# BSPD_v7b.net
KiCad netlist of a schematic drawn in EAGLE
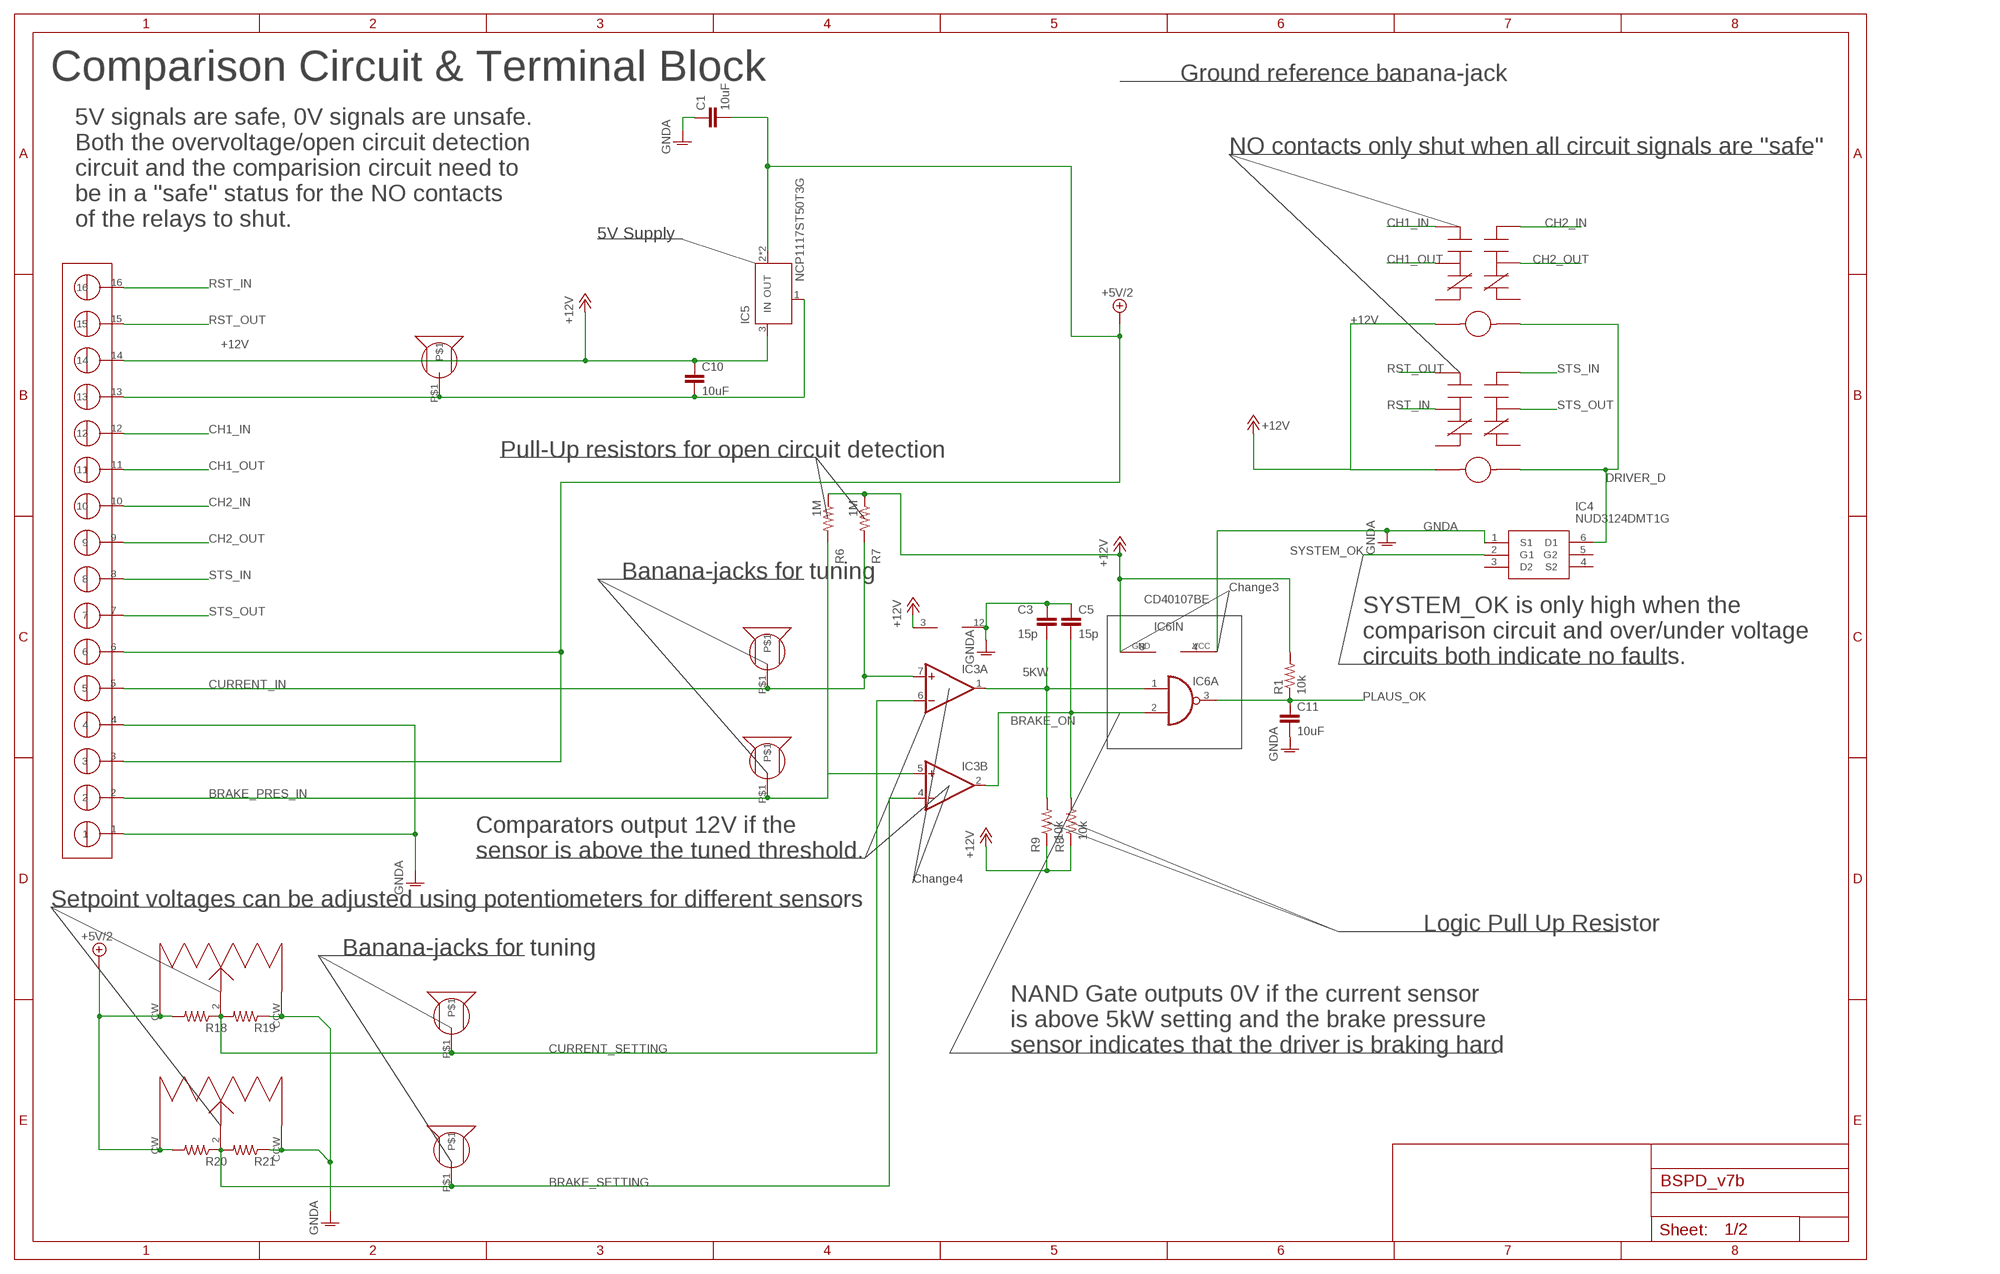
[diagram p0: schematic, sheet 1]
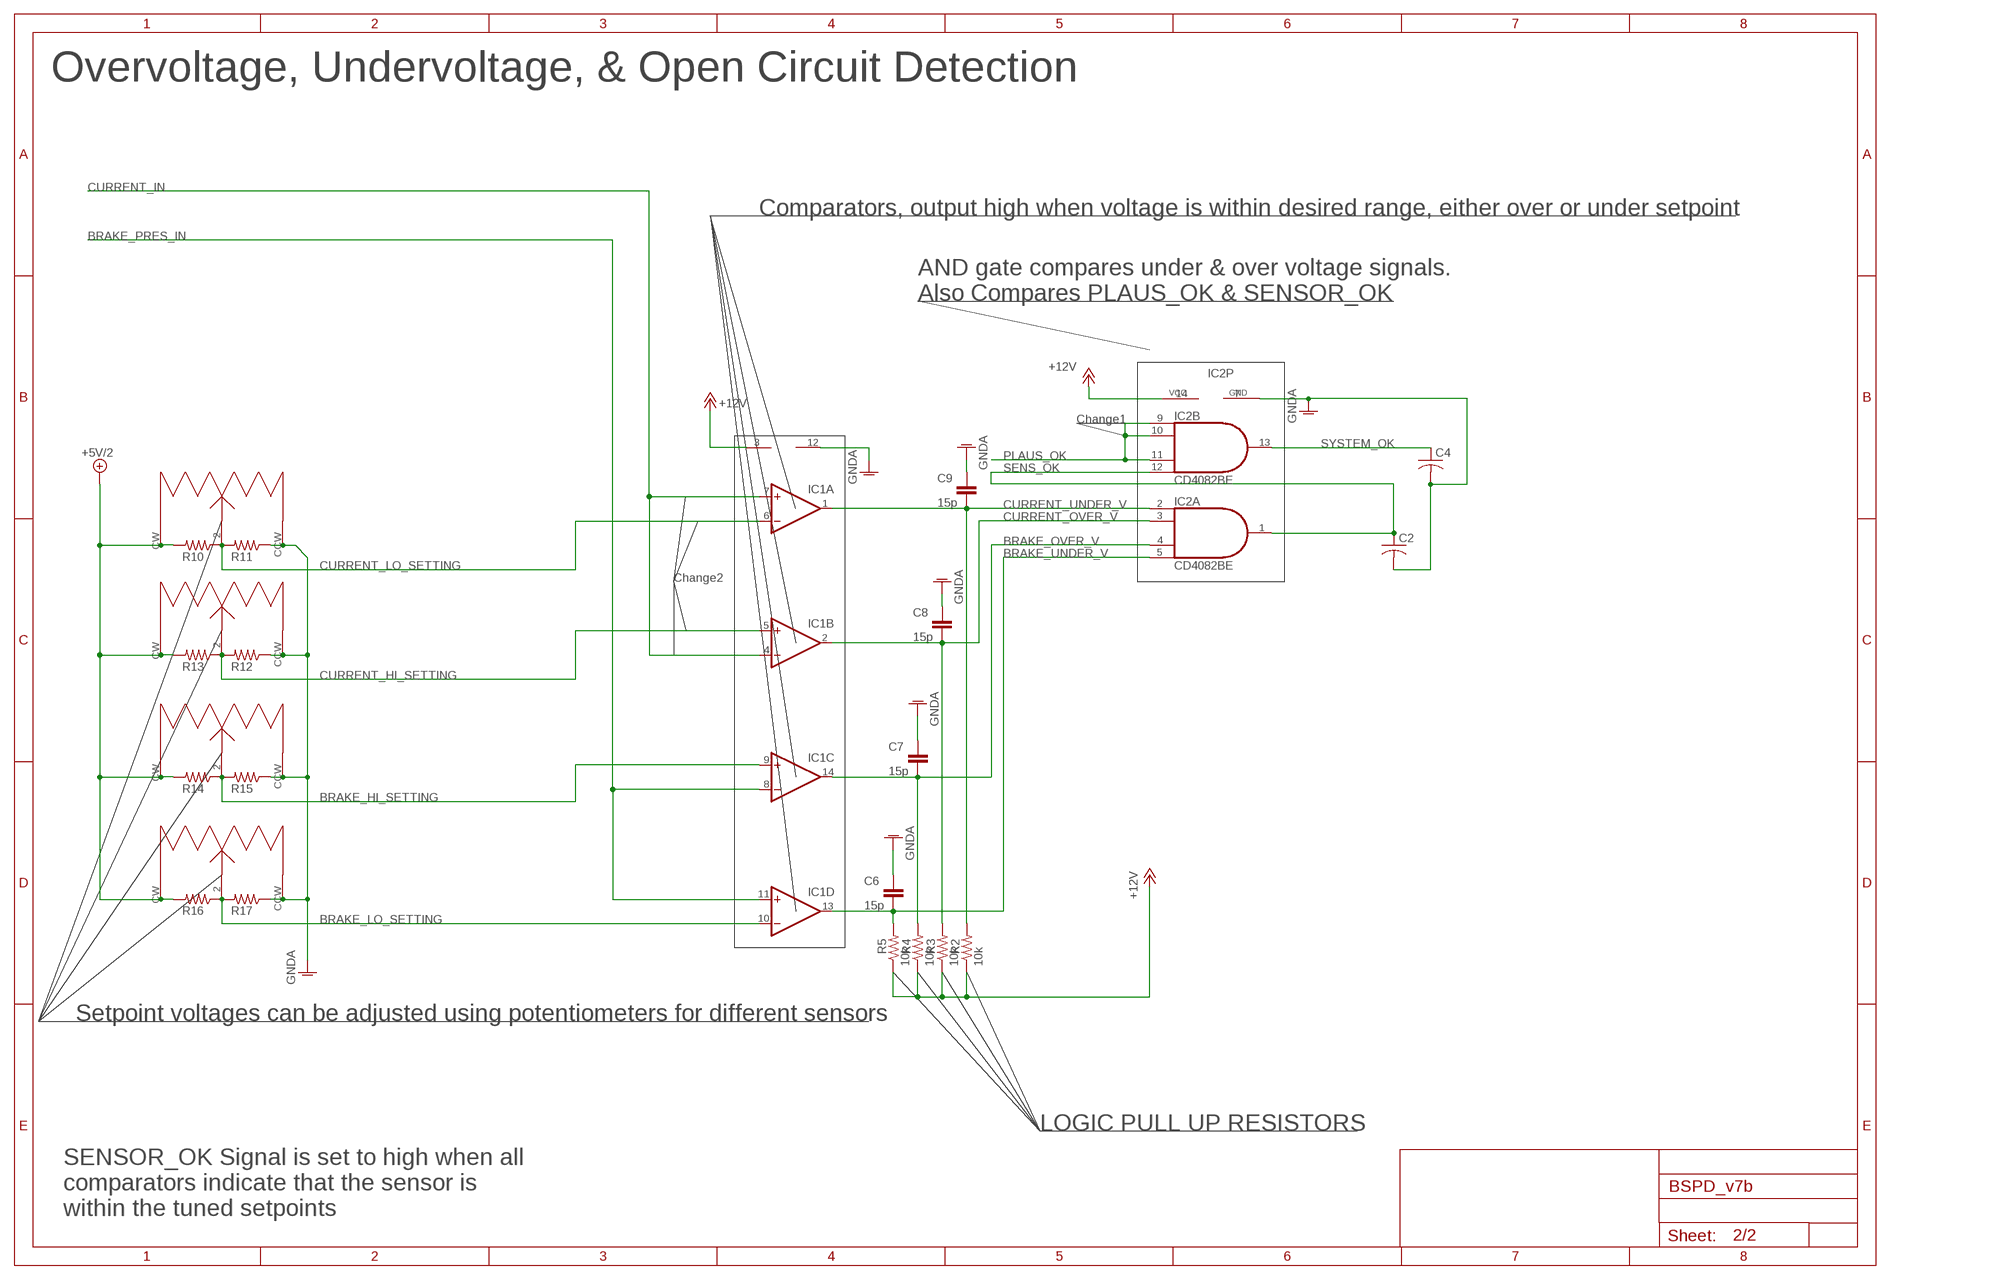
[diagram p1: schematic, sheet 2]

(export (version "E")
  (design (tool "Eeschema 10.0.6"))
  (components
    (comp (ref "C2")
      (value "C-USC0805")
      (footprint "eagle-import:C0805")
      (libsource (lib "eagle-import") (part "C-USC0805"))
    )
    (comp (ref "C4")
      (value "C-USC0805")
      (footprint "eagle-import:C0805")
      (libsource (lib "eagle-import") (part "C-USC0805"))
    )
    (comp (ref "C6")
      (value "15p")
      (footprint "eagle-import:C0805")
      (libsource (lib "eagle-import") (part "C-EUC0805"))
    )
    (comp (ref "C7")
      (value "15p")
      (footprint "eagle-import:C0805")
      (libsource (lib "eagle-import") (part "C-EUC0805"))
    )
    (comp (ref "C8")
      (value "15p")
      (footprint "eagle-import:C0805")
      (libsource (lib "eagle-import") (part "C-EUC0805"))
    )
    (comp (ref "C9")
      (value "15p")
      (footprint "eagle-import:C0805")
      (libsource (lib "eagle-import") (part "C-EUC0805"))
    )
    (comp (ref "IC1")
      (value "4AMP_P11+7N")
      (footprint "eagle-import:DIL14")
      (libsource (lib "eagle-import") (part "4AMP_P11+7N"))
    )
    (comp (ref "IC2")
      (value "CD4082BE")
      (footprint "eagle-import:DIL14")
      (libsource (lib "eagle-import") (part "7421NALS"))
    )
    (comp (ref "R2")
      (value "10k")
      (footprint "eagle-import:M0805")
      (libsource (lib "eagle-import") (part "resistor_R-US_M0805"))
    )
    (comp (ref "R3")
      (value "10k")
      (footprint "eagle-import:M0805")
      (libsource (lib "eagle-import") (part "resistor_R-US_M0805"))
    )
    (comp (ref "R4")
      (value "10k")
      (footprint "eagle-import:M0805")
      (libsource (lib "eagle-import") (part "resistor_R-US_M0805"))
    )
    (comp (ref "R5")
      (value "10k")
      (footprint "eagle-import:M0805")
      (libsource (lib "eagle-import") (part "resistor_R-US_M0805"))
    )
    (comp (ref "R10")
      (value "R-US_M0805")
      (footprint "eagle-import:M0805")
      (libsource (lib "eagle-import") (part "resistor_R-US_M0805"))
    )
    (comp (ref "R11")
      (value "R-US_M0805")
      (footprint "eagle-import:M0805")
      (libsource (lib "eagle-import") (part "resistor_R-US_M0805"))
    )
    (comp (ref "R12")
      (value "R-US_M0805")
      (footprint "eagle-import:M0805")
      (libsource (lib "eagle-import") (part "resistor_R-US_M0805"))
    )
    (comp (ref "R13")
      (value "R-US_M0805")
      (footprint "eagle-import:M0805")
      (libsource (lib "eagle-import") (part "resistor_R-US_M0805"))
    )
    (comp (ref "R14")
      (value "R-US_M0805")
      (footprint "eagle-import:M0805")
      (libsource (lib "eagle-import") (part "resistor_R-US_M0805"))
    )
    (comp (ref "R15")
      (value "R-US_M0805")
      (footprint "eagle-import:M0805")
      (libsource (lib "eagle-import") (part "resistor_R-US_M0805"))
    )
    (comp (ref "R16")
      (value "R-US_M0805")
      (footprint "eagle-import:M0805")
      (libsource (lib "eagle-import") (part "resistor_R-US_M0805"))
    )
    (comp (ref "R17")
      (value "R-US_M0805")
      (footprint "eagle-import:M0805")
      (libsource (lib "eagle-import") (part "resistor_R-US_M0805"))
    )
    (comp (ref "U$6")
      (value "POT_3310Y-025-103L")
      (footprint "eagle-import:3310Y")
      (libsource (lib "eagle-import") (part "POT_3310Y-025-103L"))
    )
    (comp (ref "U$7")
      (value "POT_3310Y-025-103L")
      (footprint "eagle-import:3310Y")
      (libsource (lib "eagle-import") (part "POT_3310Y-025-103L"))
    )
    (comp (ref "U$8")
      (value "POT_3310Y-025-103L")
      (footprint "eagle-import:3310Y")
      (libsource (lib "eagle-import") (part "POT_3310Y-025-103L"))
    )
    (comp (ref "U$9")
      (value "POT_3310Y-025-103L")
      (footprint "eagle-import:3310Y")
      (libsource (lib "eagle-import") (part "POT_3310Y-025-103L"))
    )
    (comp (ref "C1")
      (value "10uF")
      (footprint "eagle-import:C0805")
      (libsource (lib "eagle-import") (part "resistor_348_C-EUC0805"))
    )
    (comp (ref "C3")
      (value "15p")
      (footprint "eagle-import:C0805")
      (libsource (lib "eagle-import") (part "C-EUC0805"))
    )
    (comp (ref "C5")
      (value "15p")
      (footprint "eagle-import:C0805")
      (libsource (lib "eagle-import") (part "C-EUC0805"))
    )
    (comp (ref "C10")
      (value "10uF")
      (footprint "eagle-import:C0805")
      (libsource (lib "eagle-import") (part "resistor_348_C-EUC0805"))
    )
    (comp (ref "C11")
      (value "10uF")
      (footprint "eagle-import:C0805")
      (libsource (lib "eagle-import") (part "resistor_348_C-EUC0805"))
    )
    (comp (ref "IC3")
      (value "4AMP_P11+7N")
      (footprint "eagle-import:DIL14")
      (libsource (lib "eagle-import") (part "4AMP_P11+7N"))
    )
    (comp (ref "IC4")
      (value "NUD3124DMT1G")
      (footprint "eagle-import:SOT95P275X110-6N")
      (fields (field (name "MOUSER_PART_NUMBER") "863-NUD3124DMT1G"))
      (libsource (lib "eagle-import") (part "NUD3124DMT1G"))
    )
    (comp (ref "IC5")
      (value "NCP1117ST50T3G")
      (footprint "eagle-import:SOT223")
      (libsource (lib "eagle-import") (part "NCP1117ST50T3G"))
    )
    (comp (ref "IC6")
      (value "CD40107BE")
      (footprint "eagle-import:DIL08")
      (libsource (lib "eagle-import") (part "CD40107BE"))
    )
    (comp (ref "R1")
      (value "10k")
      (footprint "eagle-import:M0805")
      (libsource (lib "eagle-import") (part "R-US_M0805"))
    )
    (comp (ref "R6")
      (value "1M")
      (footprint "eagle-import:M0805")
      (libsource (lib "eagle-import") (part "resistor_R-US_M0805"))
    )
    (comp (ref "R7")
      (value "1M")
      (footprint "eagle-import:M0805")
      (libsource (lib "eagle-import") (part "resistor_R-US_M0805"))
    )
    (comp (ref "R8")
      (value "10k")
      (footprint "eagle-import:M0805")
      (libsource (lib "eagle-import") (part "resistor_R-US_M0805"))
    )
    (comp (ref "R9")
      (value "10k")
      (footprint "eagle-import:M0805")
      (libsource (lib "eagle-import") (part "resistor_R-US_M0805"))
    )
    (comp (ref "R18")
      (value "R-US_M0805")
      (footprint "eagle-import:M0805")
      (libsource (lib "eagle-import") (part "resistor_R-US_M0805"))
    )
    (comp (ref "R19")
      (value "R-US_M0805")
      (footprint "eagle-import:M0805")
      (libsource (lib "eagle-import") (part "resistor_R-US_M0805"))
    )
    (comp (ref "R20")
      (value "R-US_M0805")
      (footprint "eagle-import:M0805")
      (libsource (lib "eagle-import") (part "resistor_R-US_M0805"))
    )
    (comp (ref "R21")
      (value "R-US_M0805")
      (footprint "eagle-import:M0805")
      (libsource (lib "eagle-import") (part "resistor_R-US_M0805"))
    )
    (comp (ref "U$1")
      (value "BSPD_PARTS_AMPH_OQ1632500000G")
      (footprint "eagle-import:BSPD_PARTS_3_81MM_16PIN")
      (libsource (lib "eagle-import") (part "BSPD_PARTS_AMPH_OQ1632500000G"))
    )
    (comp (ref "U$4")
      (value "BSPD_PARTS_MP_BANANA_PLUG")
      (footprint "eagle-import:BSPD_PARTS_BANANA_PLUG")
      (libsource (lib "eagle-import") (part "BSPD_PARTS_MP_BANANA_PLUG"))
    )
    (comp (ref "U$10")
      (value "POT_3310Y-025-103L")
      (footprint "eagle-import:3310Y")
      (libsource (lib "eagle-import") (part "POT_3310Y-025-103L"))
    )
    (comp (ref "U$11")
      (value "POT_3310Y-025-103L")
      (footprint "eagle-import:3310Y")
      (libsource (lib "eagle-import") (part "POT_3310Y-025-103L"))
    )
    (comp (ref "U$12")
      (value "BSPD_PARTS_RLY_V23079A1001B301")
      (footprint "eagle-import:BSPD_PARTS_V23079F1101B301")
      (libsource (lib "eagle-import") (part "BSPD_PARTS_RLY_V23079A1001B301"))
    )
    (comp (ref "U$13")
      (value "BSPD_PARTS_RLY_V23079A1001B301")
      (footprint "eagle-import:BSPD_PARTS_V23079F1101B301")
      (libsource (lib "eagle-import") (part "BSPD_PARTS_RLY_V23079A1001B301"))
    )
    (comp (ref "U$18")
      (value "BSPD_PARTS_MP_BANANA_PLUG")
      (footprint "eagle-import:BSPD_PARTS_BANANA_PLUG")
      (libsource (lib "eagle-import") (part "BSPD_PARTS_MP_BANANA_PLUG"))
    )
    (comp (ref "U$19")
      (value "BSPD_PARTS_MP_BANANA_PLUG")
      (footprint "eagle-import:BSPD_PARTS_BANANA_PLUG")
      (libsource (lib "eagle-import") (part "BSPD_PARTS_MP_BANANA_PLUG"))
    )
    (comp (ref "U$21")
      (value "BSPD_PARTS_MP_BANANA_PLUG")
      (footprint "eagle-import:BSPD_PARTS_BANANA_PLUG")
      (libsource (lib "eagle-import") (part "BSPD_PARTS_MP_BANANA_PLUG"))
    )
    (comp (ref "U$22")
      (value "BSPD_PARTS_MP_BANANA_PLUG")
      (footprint "eagle-import:BSPD_PARTS_BANANA_PLUG")
      (libsource (lib "eagle-import") (part "BSPD_PARTS_MP_BANANA_PLUG"))
    )
  )
  (nets
    (net (code "1") (name "+5V{slash}2") (class "Default")
      (node (ref "C1") (pin "2") (pinfunction "2_2") (pintype "passive"))
      (node (ref "IC5") (pin "2") (pinfunction "OUT_2") (pintype "passive"))
      (node (ref "IC5") (pin "4") (pinfunction "OUT_4") (pintype "passive"))
      (node (ref "R10") (pin "2") (pinfunction "2_2") (pintype "passive"))
      (node (ref "R13") (pin "2") (pinfunction "2_2") (pintype "passive"))
      (node (ref "R14") (pin "2") (pinfunction "2_2") (pintype "passive"))
      (node (ref "R16") (pin "2") (pinfunction "2_2") (pintype "passive"))
      (node (ref "R18") (pin "2") (pinfunction "2_2") (pintype "passive"))
      (node (ref "R20") (pin "2") (pinfunction "2_2") (pintype "passive"))
      (node (ref "U$1") (pin "3") (pinfunction "3_3") (pintype "bidirectional"))
      (node (ref "U$1") (pin "6") (pinfunction "6_6") (pintype "bidirectional"))
      (node (ref "U$10") (pin "CW") (pinfunction "CW_CW") (pintype "bidirectional"))
      (node (ref "U$11") (pin "CW") (pinfunction "CW_CW") (pintype "bidirectional"))
      (node (ref "U$6") (pin "CW") (pinfunction "CW_CW") (pintype "bidirectional"))
      (node (ref "U$7") (pin "CW") (pinfunction "CW_CW") (pintype "bidirectional"))
      (node (ref "U$8") (pin "CW") (pinfunction "CW_CW") (pintype "bidirectional"))
      (node (ref "U$9") (pin "CW") (pinfunction "CW_CW") (pintype "bidirectional"))
    )
    (net (code "2") (name "+12V") (class "Default")
      (node (ref "C10") (pin "1") (pinfunction "1_1") (pintype "passive"))
      (node (ref "IC1") (pin "3") (pinfunction "V+_3") (pintype "power_in"))
      (node (ref "IC2") (pin "14") (pinfunction "VCC_14") (pintype "power_in"))
      (node (ref "IC3") (pin "3") (pinfunction "V+_3") (pintype "power_in"))
      (node (ref "IC5") (pin "3") (pinfunction "IN_3") (pintype "input"))
      (node (ref "IC6") (pin "8") (pinfunction "GND_8") (pintype "power_in"))
      (node (ref "R1") (pin "2") (pinfunction "2_2") (pintype "passive"))
      (node (ref "R2") (pin "1") (pinfunction "1_1") (pintype "passive"))
      (node (ref "R3") (pin "1") (pinfunction "1_1") (pintype "passive"))
      (node (ref "R4") (pin "1") (pinfunction "1_1") (pintype "passive"))
      (node (ref "R5") (pin "1") (pinfunction "1_1") (pintype "passive"))
      (node (ref "R6") (pin "1") (pinfunction "1_1") (pintype "passive"))
      (node (ref "R7") (pin "1") (pinfunction "1_1") (pintype "passive"))
      (node (ref "R8") (pin "1") (pinfunction "1_1") (pintype "passive"))
      (node (ref "R9") (pin "1") (pinfunction "1_1") (pintype "passive"))
      (node (ref "U$1") (pin "14") (pinfunction "14_14") (pintype "bidirectional"))
      (node (ref "U$12") (pin "1") (pinfunction "1_1") (pintype "bidirectional"))
      (node (ref "U$13") (pin "1") (pinfunction "1_1") (pintype "bidirectional"))
    )
    (net (code "3") (name "5KW") (class "Default")
      (node (ref "C3") (pin "2") (pinfunction "2_2") (pintype "passive"))
      (node (ref "IC3") (pin "1") (pinfunction "OUT_1") (pintype "output"))
      (node (ref "IC6") (pin "1") (pinfunction "I0_1") (pintype "input"))
      (node (ref "R9") (pin "2") (pinfunction "2_2") (pintype "passive"))
    )
    (net (code "4") (name "BRAKE_HI_SETTING") (class "Default")
      (node (ref "IC1") (pin "9") (pinfunction "+IN_9") (pintype "input"))
      (node (ref "R14") (pin "1") (pinfunction "1_1") (pintype "passive"))
      (node (ref "R15") (pin "2") (pinfunction "2_2") (pintype "passive"))
      (node (ref "U$8") (pin "2") (pinfunction "VO_2") (pintype "bidirectional"))
    )
    (net (code "5") (name "BRAKE_LO_SETTING") (class "Default")
      (node (ref "IC1") (pin "10") (pinfunction "-IN_10") (pintype "input"))
      (node (ref "R16") (pin "1") (pinfunction "1_1") (pintype "passive"))
      (node (ref "R17") (pin "2") (pinfunction "2_2") (pintype "passive"))
      (node (ref "U$9") (pin "2") (pinfunction "VO_2") (pintype "bidirectional"))
    )
    (net (code "6") (name "BRAKE_ON") (class "Default")
      (node (ref "C5") (pin "2") (pinfunction "2_2") (pintype "passive"))
      (node (ref "IC3") (pin "2") (pinfunction "OUT_2") (pintype "output"))
      (node (ref "IC6") (pin "2") (pinfunction "I1_2") (pintype "input"))
      (node (ref "R8") (pin "2") (pinfunction "2_2") (pintype "passive"))
    )
    (net (code "7") (name "BRAKE_OVER_V") (class "Default")
      (node (ref "C7") (pin "2") (pinfunction "2_2") (pintype "passive"))
      (node (ref "IC1") (pin "14") (pinfunction "OUT_14") (pintype "output"))
      (node (ref "IC2") (pin "4") (pinfunction "I2_4") (pintype "input"))
      (node (ref "R4") (pin "2") (pinfunction "2_2") (pintype "passive"))
    )
    (net (code "8") (name "BRAKE_PRES_IN") (class "Default")
      (node (ref "IC1") (pin "11") (pinfunction "+IN_11") (pintype "input"))
      (node (ref "IC1") (pin "8") (pinfunction "-IN_8") (pintype "input"))
      (node (ref "IC3") (pin "5") (pinfunction "+IN_5") (pintype "input"))
      (node (ref "R6") (pin "2") (pinfunction "2_2") (pintype "passive"))
      (node (ref "U$1") (pin "2") (pinfunction "2_2") (pintype "bidirectional"))
      (node (ref "U$22") (pin "P$1") (pinfunction "P$1_P$1") (pintype "bidirectional"))
    )
    (net (code "9") (name "BRAKE_SETTING") (class "Default")
      (node (ref "IC3") (pin "4") (pinfunction "-IN_4") (pintype "input"))
      (node (ref "R20") (pin "1") (pinfunction "1_1") (pintype "passive"))
      (node (ref "R21") (pin "2") (pinfunction "2_2") (pintype "passive"))
      (node (ref "U$10") (pin "2") (pinfunction "VO_2") (pintype "bidirectional"))
      (node (ref "U$19") (pin "P$1") (pinfunction "P$1_P$1") (pintype "bidirectional"))
    )
    (net (code "10") (name "BRAKE_UNDER_V") (class "Default")
      (node (ref "C6") (pin "2") (pinfunction "2_2") (pintype "passive"))
      (node (ref "IC1") (pin "13") (pinfunction "OUT_13") (pintype "output"))
      (node (ref "IC2") (pin "5") (pinfunction "I3_5") (pintype "input"))
      (node (ref "R5") (pin "2") (pinfunction "2_2") (pintype "passive"))
    )
    (net (code "11") (name "CH1_IN") (class "Default")
      (node (ref "U$1") (pin "12") (pinfunction "12_12") (pintype "bidirectional"))
      (node (ref "U$13") (pin "5") (pinfunction "5_5") (pintype "bidirectional"))
    )
    (net (code "12") (name "CH1_OUT") (class "Default")
      (node (ref "U$1") (pin "11") (pinfunction "11_11") (pintype "bidirectional"))
      (node (ref "U$13") (pin "4") (pinfunction "4_4") (pintype "bidirectional"))
    )
    (net (code "13") (name "CH2_IN") (class "Default")
      (node (ref "U$1") (pin "10") (pinfunction "10_10") (pintype "bidirectional"))
      (node (ref "U$13") (pin "8") (pinfunction "8_8") (pintype "bidirectional"))
    )
    (net (code "14") (name "CH2_OUT") (class "Default")
      (node (ref "U$1") (pin "9") (pinfunction "9_9") (pintype "bidirectional"))
      (node (ref "U$13") (pin "9") (pinfunction "9_9") (pintype "bidirectional"))
    )
    (net (code "15") (name "CURRENT_HI_SETTING") (class "Default")
      (node (ref "IC1") (pin "5") (pinfunction "+IN_5") (pintype "input"))
      (node (ref "R12") (pin "2") (pinfunction "2_2") (pintype "passive"))
      (node (ref "R13") (pin "1") (pinfunction "1_1") (pintype "passive"))
      (node (ref "U$7") (pin "2") (pinfunction "VO_2") (pintype "bidirectional"))
    )
    (net (code "16") (name "CURRENT_IN") (class "Default")
      (node (ref "IC1") (pin "4") (pinfunction "-IN_4") (pintype "input"))
      (node (ref "IC1") (pin "7") (pinfunction "+IN_7") (pintype "input"))
      (node (ref "IC3") (pin "7") (pinfunction "+IN_7") (pintype "input"))
      (node (ref "R7") (pin "2") (pinfunction "2_2") (pintype "passive"))
      (node (ref "U$1") (pin "5") (pinfunction "5_5") (pintype "bidirectional"))
      (node (ref "U$21") (pin "P$1") (pinfunction "P$1_P$1") (pintype "bidirectional"))
    )
    (net (code "17") (name "CURRENT_LO_SETTING") (class "Default")
      (node (ref "IC1") (pin "6") (pinfunction "-IN_6") (pintype "input"))
      (node (ref "R10") (pin "1") (pinfunction "1_1") (pintype "passive"))
      (node (ref "R11") (pin "2") (pinfunction "2_2") (pintype "passive"))
      (node (ref "U$6") (pin "2") (pinfunction "VO_2") (pintype "bidirectional"))
    )
    (net (code "18") (name "CURRENT_OVER_V") (class "Default")
      (node (ref "C8") (pin "2") (pinfunction "2_2") (pintype "passive"))
      (node (ref "IC1") (pin "2") (pinfunction "OUT_2") (pintype "output"))
      (node (ref "IC2") (pin "3") (pinfunction "I1_3") (pintype "input"))
      (node (ref "R3") (pin "2") (pinfunction "2_2") (pintype "passive"))
    )
    (net (code "19") (name "CURRENT_SETTING") (class "Default")
      (node (ref "IC3") (pin "6") (pinfunction "-IN_6") (pintype "input"))
      (node (ref "R18") (pin "1") (pinfunction "1_1") (pintype "passive"))
      (node (ref "R19") (pin "2") (pinfunction "2_2") (pintype "passive"))
      (node (ref "U$11") (pin "2") (pinfunction "VO_2") (pintype "bidirectional"))
      (node (ref "U$18") (pin "P$1") (pinfunction "P$1_P$1") (pintype "bidirectional"))
    )
    (net (code "20") (name "CURRENT_UNDER_V") (class "Default")
      (node (ref "C9") (pin "2") (pinfunction "2_2") (pintype "passive"))
      (node (ref "IC1") (pin "1") (pinfunction "OUT_1") (pintype "output"))
      (node (ref "IC2") (pin "2") (pinfunction "I0_2") (pintype "input"))
      (node (ref "R2") (pin "2") (pinfunction "2_2") (pintype "passive"))
    )
    (net (code "21") (name "DRIVER_D") (class "Default")
      (node (ref "IC4") (pin "6") (pinfunction "D1_6") (pintype "bidirectional"))
      (node (ref "U$12") (pin "12") (pinfunction "12_12") (pintype "bidirectional"))
      (node (ref "U$13") (pin "12") (pinfunction "12_12") (pintype "bidirectional"))
    )
    (net (code "22") (name "GNDA") (class "Default")
      (node (ref "C1") (pin "1") (pinfunction "1_1") (pintype "passive"))
      (node (ref "C10") (pin "2") (pinfunction "2_2") (pintype "passive"))
      (node (ref "C11") (pin "2") (pinfunction "2_2") (pintype "passive"))
      (node (ref "C2") (pin "2") (pinfunction "2_2") (pintype "passive"))
      (node (ref "C3") (pin "1") (pinfunction "1_1") (pintype "passive"))
      (node (ref "C4") (pin "2") (pinfunction "2_2") (pintype "passive"))
      (node (ref "C5") (pin "1") (pinfunction "1_1") (pintype "passive"))
      (node (ref "C6") (pin "1") (pinfunction "1_1") (pintype "passive"))
      (node (ref "C7") (pin "1") (pinfunction "1_1") (pintype "passive"))
      (node (ref "C8") (pin "1") (pinfunction "1_1") (pintype "passive"))
      (node (ref "C9") (pin "1") (pinfunction "1_1") (pintype "passive"))
      (node (ref "IC1") (pin "12") (pinfunction "V-_12") (pintype "power_in"))
      (node (ref "IC2") (pin "7") (pinfunction "GND_7") (pintype "power_in"))
      (node (ref "IC3") (pin "12") (pinfunction "V-_12") (pintype "power_in"))
      (node (ref "IC4") (pin "1") (pinfunction "S1_1") (pintype "bidirectional"))
      (node (ref "IC5") (pin "1") (pinfunction "GND_1") (pintype "power_in"))
      (node (ref "IC6") (pin "4") (pinfunction "VCC_4") (pintype "power_in"))
      (node (ref "R11") (pin "1") (pinfunction "1_1") (pintype "passive"))
      (node (ref "R12") (pin "1") (pinfunction "1_1") (pintype "passive"))
      (node (ref "R15") (pin "1") (pinfunction "1_1") (pintype "passive"))
      (node (ref "R17") (pin "1") (pinfunction "1_1") (pintype "passive"))
      (node (ref "R19") (pin "1") (pinfunction "1_1") (pintype "passive"))
      (node (ref "R21") (pin "1") (pinfunction "1_1") (pintype "passive"))
      (node (ref "U$1") (pin "1") (pinfunction "1_1") (pintype "bidirectional"))
      (node (ref "U$1") (pin "13") (pinfunction "13_13") (pintype "bidirectional"))
      (node (ref "U$1") (pin "4") (pinfunction "4_4") (pintype "bidirectional"))
      (node (ref "U$10") (pin "CCW") (pinfunction "CCW_CCW") (pintype "bidirectional"))
      (node (ref "U$11") (pin "CCW") (pinfunction "CCW_CCW") (pintype "bidirectional"))
      (node (ref "U$4") (pin "P$1") (pinfunction "P$1_P$1") (pintype "bidirectional"))
      (node (ref "U$6") (pin "CCW") (pinfunction "CCW_CCW") (pintype "bidirectional"))
      (node (ref "U$7") (pin "CCW") (pinfunction "CCW_CCW") (pintype "bidirectional"))
      (node (ref "U$8") (pin "CCW") (pinfunction "CCW_CCW") (pintype "bidirectional"))
      (node (ref "U$9") (pin "CCW") (pinfunction "CCW_CCW") (pintype "bidirectional"))
    )
    (net (code "23") (name "PLAUS_OK") (class "Default")
      (node (ref "C11") (pin "1") (pinfunction "1_1") (pintype "passive"))
      (node (ref "IC2") (pin "10") (pinfunction "I1_10") (pintype "input"))
      (node (ref "IC2") (pin "11") (pinfunction "I2_11") (pintype "input"))
      (node (ref "IC2") (pin "9") (pinfunction "I0_9") (pintype "input"))
      (node (ref "IC6") (pin "3") (pinfunction "O_3") (pintype "output"))
      (node (ref "R1") (pin "1") (pinfunction "1_1") (pintype "passive"))
    )
    (net (code "24") (name "RST_IN") (class "Default")
      (node (ref "U$1") (pin "16") (pinfunction "16_16") (pintype "bidirectional"))
      (node (ref "U$12") (pin "4") (pinfunction "4_4") (pintype "bidirectional"))
    )
    (net (code "25") (name "RST_OUT") (class "Default")
      (node (ref "U$1") (pin "15") (pinfunction "15_15") (pintype "bidirectional"))
      (node (ref "U$12") (pin "5") (pinfunction "5_5") (pintype "bidirectional"))
    )
    (net (code "26") (name "SENS_OK") (class "Default")
      (node (ref "C2") (pin "1") (pinfunction "1_1") (pintype "passive"))
      (node (ref "IC2") (pin "1") (pinfunction "O_1") (pintype "output"))
      (node (ref "IC2") (pin "12") (pinfunction "I3_12") (pintype "input"))
    )
    (net (code "27") (name "STS_IN") (class "Default")
      (node (ref "U$1") (pin "8") (pinfunction "8_8") (pintype "bidirectional"))
      (node (ref "U$12") (pin "8") (pinfunction "8_8") (pintype "bidirectional"))
    )
    (net (code "28") (name "STS_OUT") (class "Default")
      (node (ref "U$1") (pin "7") (pinfunction "7_7") (pintype "bidirectional"))
      (node (ref "U$12") (pin "9") (pinfunction "9_9") (pintype "bidirectional"))
    )
    (net (code "29") (name "SYSTEM_OK") (class "Default")
      (node (ref "C4") (pin "1") (pinfunction "1_1") (pintype "passive"))
      (node (ref "IC2") (pin "13") (pinfunction "O_13") (pintype "output"))
      (node (ref "IC4") (pin "2") (pinfunction "G1_2") (pintype "bidirectional"))
    )
    (net (code "30") (name "unconnected-(IC4-D2-Pad3)") (class "Default")
      (node (ref "IC4") (pin "3") (pinfunction "D2_3") (pintype "bidirectional"))
    )
    (net (code "31") (name "unconnected-(IC4-G2-Pad5)") (class "Default")
      (node (ref "IC4") (pin "5") (pinfunction "G2_5") (pintype "bidirectional"))
    )
    (net (code "32") (name "unconnected-(IC4-S2-Pad4)") (class "Default")
      (node (ref "IC4") (pin "4") (pinfunction "S2_4") (pintype "bidirectional"))
    )
    (net (code "33") (name "unconnected-(U$12-Pad3)") (class "Default")
      (node (ref "U$12") (pin "3") (pinfunction "3_3") (pintype "bidirectional"))
    )
    (net (code "34") (name "unconnected-(U$12-Pad10)") (class "Default")
      (node (ref "U$12") (pin "10") (pinfunction "10_10") (pintype "bidirectional"))
    )
    (net (code "35") (name "unconnected-(U$13-Pad3)") (class "Default")
      (node (ref "U$13") (pin "3") (pinfunction "3_3") (pintype "bidirectional"))
    )
    (net (code "36") (name "unconnected-(U$13-Pad10)") (class "Default")
      (node (ref "U$13") (pin "10") (pinfunction "10_10") (pintype "bidirectional"))
    )
  )
)
